# Adafruit_AP6302.net
KiCad netlist of a schematic drawn in EAGLE
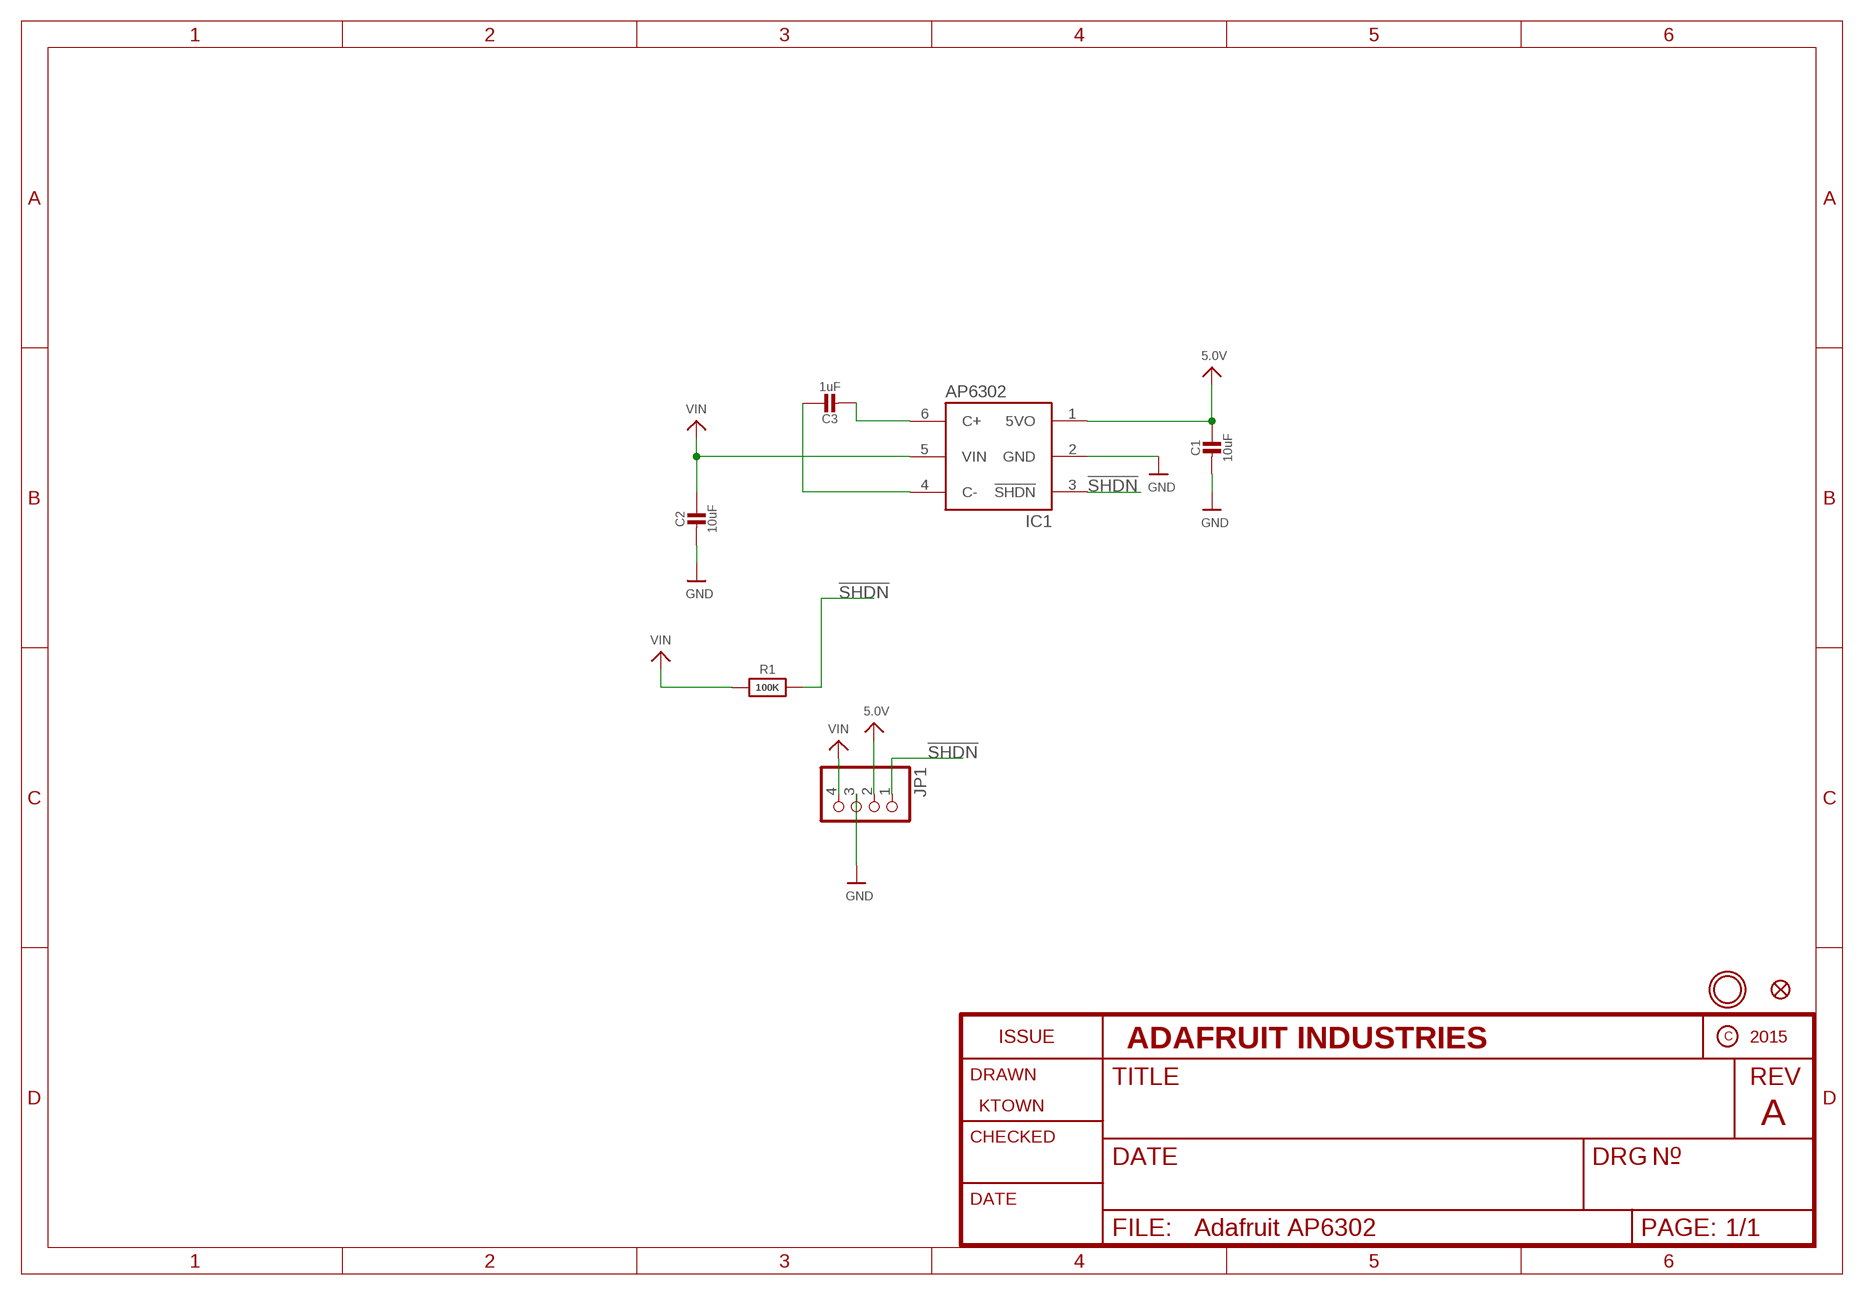
[diagram p0: schematic, sheet 1]

(export (version "E")
  (design (tool "Eeschema 10.0.6"))
  (components
    (comp (ref "C1")
      (value "10uF")
      (footprint "eagle-import:0805-NO")
      (libsource (lib "eagle-import") (part "CAP_CERAMIC0805-NOOUTLINE"))
    )
    (comp (ref "C2")
      (value "10uF")
      (footprint "eagle-import:0805-NO")
      (libsource (lib "eagle-import") (part "CAP_CERAMIC0805-NOOUTLINE"))
    )
    (comp (ref "C3")
      (value "1uF")
      (footprint "eagle-import:0805-NO")
      (libsource (lib "eagle-import") (part "CAP_CERAMIC0805-NOOUTLINE"))
    )
    (comp (ref "FID1")
      (value "FIDUCIAL\"\"")
      (footprint "eagle-import:FIDUCIAL_1MM")
      (libsource (lib "eagle-import") (part "FIDUCIAL{dblquote}{dblquote}"))
    )
    (comp (ref "IC1")
      (value "AP3602")
      (footprint "eagle-import:SOT23-6")
      (libsource (lib "eagle-import") (part "AP3602"))
    )
    (comp (ref "JP1")
      (value "HEADER-1X4ROUND")
      (footprint "eagle-import:1X04_ROUND")
      (libsource (lib "eagle-import") (part "HEADER-1X4ROUND"))
    )
    (comp (ref "R1")
      (value "100K")
      (footprint "eagle-import:0805-NO")
      (libsource (lib "eagle-import") (part "RESISTOR0805_NOOUTLINE"))
    )
    (comp (ref "U$9")
      (value "MOUNTINGHOLE2.5")
      (footprint "eagle-import:MOUNTINGHOLE_2.5_PLATED")
      (libsource (lib "eagle-import") (part "MOUNTINGHOLE2.5"))
    )
  )
  (nets
    (net (code "1") (name "/~{SHDN}") (class "Default")
      (node (ref "IC1") (pin "3") (pinfunction "~{SHDN}_3") (pintype "input"))
      (node (ref "JP1") (pin "1") (pinfunction "1_1") (pintype "passive"))
      (node (ref "R1") (pin "2") (pinfunction "2_2") (pintype "passive"))
    )
    (net (code "2") (name "5.0V") (class "Default")
      (node (ref "C1") (pin "1") (pinfunction "1_1") (pintype "passive"))
      (node (ref "IC1") (pin "1") (pinfunction "5VO_1") (pintype "power_in"))
      (node (ref "JP1") (pin "2") (pinfunction "2_2") (pintype "passive"))
    )
    (net (code "3") (name "GND") (class "Default")
      (node (ref "C1") (pin "2") (pinfunction "2_2") (pintype "passive"))
      (node (ref "C2") (pin "2") (pinfunction "2_2") (pintype "passive"))
      (node (ref "IC1") (pin "2") (pinfunction "GND_2") (pintype "power_in"))
      (node (ref "JP1") (pin "3") (pinfunction "3_3") (pintype "passive"))
    )
    (net (code "4") (name "Net-(IC1-C+)") (class "Default")
      (node (ref "C3") (pin "2") (pinfunction "2_2") (pintype "passive"))
      (node (ref "IC1") (pin "6") (pinfunction "C+_6") (pintype "bidirectional"))
    )
    (net (code "5") (name "Net-(IC1-C-)") (class "Default")
      (node (ref "C3") (pin "1") (pinfunction "1_1") (pintype "passive"))
      (node (ref "IC1") (pin "4") (pinfunction "C-_4") (pintype "bidirectional"))
    )
    (net (code "6") (name "VIN") (class "Default")
      (node (ref "C2") (pin "1") (pinfunction "1_1") (pintype "passive"))
      (node (ref "IC1") (pin "5") (pinfunction "VIN_5") (pintype "power_in"))
      (node (ref "JP1") (pin "4") (pinfunction "4_4") (pintype "passive"))
      (node (ref "R1") (pin "1") (pinfunction "1_1") (pintype "passive"))
    )
  )
)
